# ArduinoProMini_Schematic.net
KiCad netlist of a schematic drawn in Altium Designer
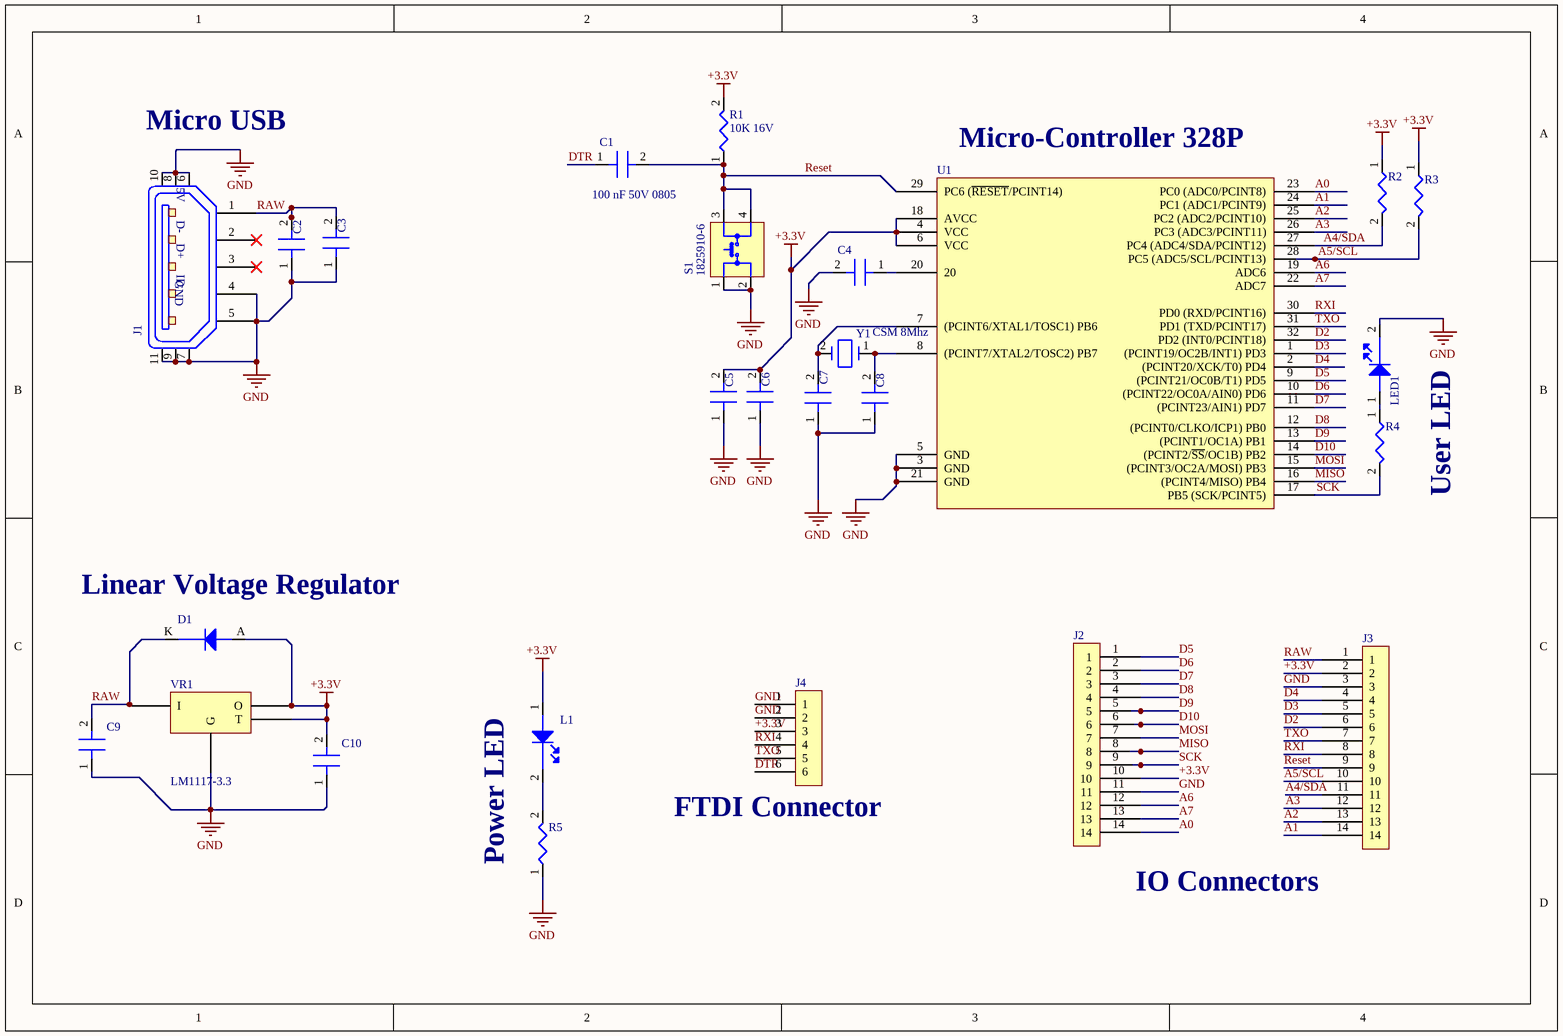
[diagram p0: ArduinoProMini_Schematic.SchDoc]

(export (version "E")
  (design (tool "Eeschema 10.0.6"))
  (components
    (comp (ref "C1")
      (value "100 nF 50V 0805")
      (footprint "C 0805")
      (description "Multilayer Ceramic Capacitor, 0.1 uF, 50 V, -20%, +80%, Y5V, 0805 [2012 Metric]")
      (fields
        (field (name "MANUFACTURER") "KEMET")
        (field (name "MANUFACTURER PART NUMBER") "C0805C104Z5VACTU")
      )
      (libsource (lib "ArduinoProMini_SchematicLib") (part "C0805C104Z5VACTU"))
    )
    (comp (ref "C2")
      (value "100nF")
      (footprint "C 0805")
      (description "Multilayer Ceramic Capacitor, 0.1 uF, 50 V, -20%, +80%, Y5V, 0805 [2012 Metric]")
      (fields
        (field (name "MANUFACTURER") "KEMET")
        (field (name "MANUFACTURER PART NUMBER") "C0805C104Z5VACTU")
      )
      (libsource (lib "ArduinoProMini_SchematicLib") (part "C0805C104Z5VACTU"))
    )
    (comp (ref "C3")
      (value "100nF")
      (footprint "C 0805")
      (description "Multilayer Ceramic Capacitor, 0.1 uF, 50 V, -20%, +80%, Y5V, 0805 [2012 Metric]")
      (fields
        (field (name "MANUFACTURER") "KEMET")
        (field (name "MANUFACTURER PART NUMBER") "C0805C104Z5VACTU")
      )
      (libsource (lib "ArduinoProMini_SchematicLib") (part "C0805C104Z5VACTU"))
    )
    (comp (ref "C4")
      (value "100 nF 50V 0805")
      (footprint "C 0805")
      (description "Multilayer Ceramic Capacitor, 0.1 uF, 50 V, -20%, +80%, Y5V, 0805 [2012 Metric]")
      (fields
        (field (name "MANUFACTURER") "KEMET")
        (field (name "MANUFACTURER PART NUMBER") "C0805C104Z5VACTU")
      )
      (libsource (lib "ArduinoProMini_SchematicLib") (part "C0805C104Z5VACTU"))
    )
    (comp (ref "C5")
      (value "100 nF 50V 0805")
      (footprint "C 0805")
      (description "Multilayer Ceramic Capacitor, 0.1 uF, 50 V, -20%, +80%, Y5V, 0805 [2012 Metric]")
      (fields
        (field (name "MANUFACTURER") "KEMET")
        (field (name "MANUFACTURER PART NUMBER") "C0805C104Z5VACTU")
      )
      (libsource (lib "ArduinoProMini_SchematicLib") (part "C0805C104Z5VACTU"))
    )
    (comp (ref "C6")
      (value "100 nF 50V 0805")
      (footprint "C 0805")
      (description "Multilayer Ceramic Capacitor, 0.1 uF, 50 V, -20%, +80%, Y5V, 0805 [2012 Metric]")
      (fields
        (field (name "MANUFACTURER") "KEMET")
        (field (name "MANUFACTURER PART NUMBER") "C0805C104Z5VACTU")
      )
      (libsource (lib "ArduinoProMini_SchematicLib") (part "C0805C104Z5VACTU"))
    )
    (comp (ref "C7")
      (value "18pF")
      (footprint "C 0805")
      (description "Multilayer Ceramic Capacitor, 18 pF, 50 V, ± 5%, C0G (NP0), 0805 [2012 Metric]")
      (fields
        (field (name "MANUFACTURER") "Yageo")
        (field (name "MANUFACTURER PART NUMBER") "CC0805JRNPO9BN180")
      )
      (libsource (lib "ArduinoProMini_SchematicLib") (part "CC0805JRNPO9BN180"))
    )
    (comp (ref "C8")
      (value "18pF")
      (footprint "C 0805")
      (description "Multilayer Ceramic Capacitor, 18 pF, 50 V, ± 5%, C0G (NP0), 0805 [2012 Metric]")
      (fields
        (field (name "MANUFACTURER") "Yageo")
        (field (name "MANUFACTURER PART NUMBER") "CC0805JRNPO9BN180")
      )
      (libsource (lib "ArduinoProMini_SchematicLib") (part "CC0805JRNPO9BN180"))
    )
    (comp (ref "C9")
      (value "10uF 16V")
      (footprint "C 0805")
      (description "Multilayer Ceramic Capacitor, 10 uF, 16 V, ± 10%, X5R, 0805 [2012 Metric]")
      (fields
        (field (name "MANUFACTURER") "KEMET")
        (field (name "MANUFACTURER PART NUMBER") "C0805C106K4PACTU")
      )
      (libsource (lib "ArduinoProMini_SchematicLib") (part "C0805C106K4PACTU"))
    )
    (comp (ref "C10")
      (value "10uF")
      (footprint "C 0805")
      (description "Multilayer Ceramic Capacitor, 10 uF, 16 V, ± 10%, X5R, 0805 [2012 Metric]")
      (fields
        (field (name "MANUFACTURER") "KEMET")
        (field (name "MANUFACTURER PART NUMBER") "C0805C106K4PACTU")
      )
      (libsource (lib "ArduinoProMini_SchematicLib") (part "C0805C106K4PACTU"))
    )
    (comp (ref "D1")
      (value "1N4148")
      (footprint "DIode 1N4148")
      (description "Rectifier Diode Switching 75V 0.2A 5ns 2-Pin DO-213AA Bag")
      (fields
        (field (name "MANUFACTURER") "Microsemi")
        (field (name "MANUFACTURER PART NUMBER") "1N4148UR-1")
      )
      (libsource (lib "ArduinoProMini_SchematicLib") (part "1N4148UR-1"))
    )
    (comp (ref "J1")
      (value "~")
      (footprint "Micro-USB-Type-B-FP")
      (description "CONN USB MICRO B RECPT SMT R/A")
      (fields
        (field (name "MANUFACTURER") "Amphenol ICC / FCI")
        (field (name "MANUFACTURER PART NUMBER") "10118194-0001LF")
      )
      (libsource (lib "ArduinoProMini_SchematicLib") (part "Micro-USB-Type-B-SCH"))
    )
    (comp (ref "J2")
      (value "Header 1*14 Male 2.54")
      (footprint "Header Male 1x14 2.54")
      (description "Conn Unshrouded Header HDR 14 POS 2.54mm Solder ST Thru-Hole Bag")
      (fields
        (field (name "MANUFACTURER") "Adam Equipment")
        (field (name "MANUFACTURER PART NUMBER") "PH1-14-UA")
      )
      (libsource (lib "") (part "PH1-14-UA_1"))
    )
    (comp (ref "J3")
      (value "Header 1*14 Male 2.54")
      (footprint "Header Male 1x14 2.54")
      (description "Conn Unshrouded Header HDR 14 POS 2.54mm Solder ST Thru-Hole Bag")
      (fields
        (field (name "MANUFACTURER") "Adam Equipment")
        (field (name "MANUFACTURER PART NUMBER") "PH1-14-UA")
      )
      (libsource (lib "ArduinoProMini_SchematicLib") (part "PH1-14-UA"))
    )
    (comp (ref "J4")
      (value "Header 1*6 Female")
      (footprint "Header Female 1x6-254")
      (description "2.54mm (0.1\") Pitch SIL Vertical PC Tail Socket Assembly, tin, 6 contacts")
      (fields (field (name "MANUFACTURER") "Harwin") (field (name "MANUFACTURER PART NUMBER") "M20-7820646"))
      (libsource (lib "ArduinoProMini_SchematicLib") (part "M20-7820646"))
    )
    (comp (ref "L1")
      (value "LED Blue 0603")
      (footprint "LED 0603")
      (description "LED BLUE CLEAR 0603 SMD")
      (fields
        (field (name "MANUFACTURER") "Vishay Lite-On")
        (field (name "MANUFACTURER PART NUMBER") "LTST-C194TBKT")
      )
      (libsource (lib "ArduinoProMini_SchematicLib") (part "LTST-C194TBKT"))
    )
    (comp (ref "LED1")
      (value "LED White 0603")
      (footprint "LED 0603")
      (fields (field (name "MANUFACTURER") "Inolux") (field (name "MANUFACTURER PART NUMBER") "IN-S63AT5UW"))
      (libsource (lib "ArduinoProMini_SchematicLib") (part "IN-S63AT5UW"))
    )
    (comp (ref "R1")
      (value "10K 16V")
      (footprint "R 0805")
      (description "SMD Chip Resistor, 10 kOhm, ± 1%, 125 mW, 0805 [2012 Metric], Thick Film, General Purpose")
      (fields
        (field (name "MANUFACTURER") "Yageo")
        (field (name "MANUFACTURER PART NUMBER") "RC0805FR-0710KL")
      )
      (libsource (lib "ArduinoProMini_SchematicLib") (part "RC0805FR-0710KL"))
    )
    (comp (ref "R2")
      (value "10K 16V")
      (footprint "R 0805")
      (description "SMD Chip Resistor, 10 kOhm, ± 1%, 125 mW, 0805 [2012 Metric], Thick Film, General Purpose")
      (fields
        (field (name "MANUFACTURER") "Yageo")
        (field (name "MANUFACTURER PART NUMBER") "RC0805FR-0710KL")
      )
      (libsource (lib "ArduinoProMini_SchematicLib") (part "RC0805FR-0710KL"))
    )
    (comp (ref "R3")
      (value "10K 16V")
      (footprint "R 0805")
      (description "SMD Chip Resistor, 10 kOhm, ± 1%, 125 mW, 0805 [2012 Metric], Thick Film, General Purpose")
      (fields
        (field (name "MANUFACTURER") "Yageo")
        (field (name "MANUFACTURER PART NUMBER") "RC0805FR-0710KL")
      )
      (libsource (lib "ArduinoProMini_SchematicLib") (part "RC0805FR-0710KL"))
    )
    (comp (ref "R4")
      (value "330R 150V")
      (footprint "R 0805")
      (description "SMD Chip Resistor, 330 Ohm, ± 5%, 125 mW, 0805 [2012 Metric], Thick Film, General Purpose")
      (fields
        (field (name "MANUFACTURER") "Yageo")
        (field (name "MANUFACTURER PART NUMBER") "RC0805JR-07330RL")
      )
      (libsource (lib "ArduinoProMini_SchematicLib") (part "RC0805JR-07330RL"))
    )
    (comp (ref "R5")
      (value "330R 150V")
      (footprint "R 0805")
      (description "SMD Chip Resistor, 330 Ohm, ± 5%, 125 mW, 0805 [2012 Metric], Thick Film, General Purpose")
      (fields
        (field (name "MANUFACTURER") "Yageo")
        (field (name "MANUFACTURER PART NUMBER") "RC0805JR-07330RL")
      )
      (libsource (lib "ArduinoProMini_SchematicLib") (part "RC0805JR-07330RL"))
    )
    (comp (ref "S1")
      (value "1825910-6")
      (footprint "SW-1825910-6")
      (description "Alcoswitch, Switch, Pushbutton, Tactile, SPST, 50mA, Thru Hole, 6mm ¦ TE Connectivity FSM4JH")
      (fields (field (name "MANUFACTURER") "TE Connectivity Alcoswitch"))
      (libsource (lib "ArduinoProMini_SchematicLib") (part "1825910-6"))
    )
    (comp (ref "U1")
      (value "ATMEGA328P-AUR")
      (footprint "TQFP-32")
      (description "1.8V~5.5V AVR 2MHz 23 TQFP-32 Microcontroller Units (MCUs/MPUs/SOCs) ROHS")
      (fields (field (name "MANUFACTURER") "Microchip"))
      (libsource (lib "ArduinoProMini_SchematicLib") (part "ATMEGA328P-AUR"))
    )
    (comp (ref "VR1")
      (value "LM1117-3.3")
      (footprint "LM1117-SOT223")
      (description "Positive Voltage Regulator, LDO, 3.3V, 0.8A, 1%, 1.2V dropout, 0÷125°C; LM1117MPX-3.3/NOPB")
      (fields
        (field (name "MANUFACTURER") "Texas Instruments")
        (field (name "MANUFACTURER PART NUMBER") "LM1117MPX-3.3/NOPB")
      )
      (libsource (lib "ArduinoProMini_SchematicLib") (part "LM1117MPX-3.3/NOPB"))
    )
    (comp (ref "Y1")
      (value "CSM 8Mhz")
      (footprint "Crystal CSM-7X")
      (description "Crystal 8MHz ±30ppm (Tol) ±50ppm (Stability) 18pF FUND 60Ohm 2-Pin HC-49/USX SMD T/R")
      (fields
        (field (name "MANUFACTURER") "ECS International")
        (field (name "MANUFACTURER PART NUMBER") "ECS-80-18-5PX-TR")
      )
      (libsource (lib "ArduinoProMini_SchematicLib") (part "ECS-80-18-5PX-TR"))
    )
  )
  (nets
    (net (code "1") (name "+3.3V") (class "Default")
      (node (ref "C10") (pin "2") (pinfunction "2_2") (pintype "passive"))
      (node (ref "C5") (pin "2") (pinfunction "2_2") (pintype "passive"))
      (node (ref "C6") (pin "2") (pinfunction "2_2") (pintype "passive"))
      (node (ref "D1") (pin "A") (pinfunction "anode_A") (pintype "passive"))
      (node (ref "J2") (pin "10") (pinfunction "10_10") (pintype "passive"))
      (node (ref "J3") (pin "2") (pinfunction "2_2") (pintype "passive"))
      (node (ref "J4") (pin "3") (pinfunction "3_3") (pintype "passive"))
      (node (ref "L1") (pin "1") (pinfunction "anode_1") (pintype "passive"))
      (node (ref "R1") (pin "2") (pinfunction "2_2") (pintype "passive"))
      (node (ref "R2") (pin "1") (pinfunction "1_1") (pintype "passive"))
      (node (ref "R3") (pin "1") (pinfunction "1_1") (pintype "passive"))
      (node (ref "U1") (pin "18") (pinfunction "AVCC_18") (pintype "passive"))
      (node (ref "U1") (pin "4") (pinfunction "VCC_4") (pintype "passive"))
      (node (ref "U1") (pin "6") (pinfunction "VCC_6") (pintype "passive"))
      (node (ref "VR1") (pin "2") (pinfunction "O_2") (pintype "passive"))
      (node (ref "VR1") (pin "4") (pinfunction "T_4") (pintype "passive"))
    )
    (net (code "2") (name "/A0") (class "Default")
      (node (ref "J2") (pin "14") (pinfunction "14_14") (pintype "passive"))
      (node (ref "U1") (pin "23") (pinfunction "PC0_(ADC0/PCINT8)_23") (pintype "passive"))
    )
    (net (code "3") (name "/A1") (class "Default")
      (node (ref "J3") (pin "14") (pinfunction "14_14") (pintype "passive"))
      (node (ref "U1") (pin "24") (pinfunction "PC1_(ADC1/PCINT9)_24") (pintype "passive"))
    )
    (net (code "4") (name "/A2") (class "Default")
      (node (ref "J3") (pin "13") (pinfunction "13_13") (pintype "passive"))
      (node (ref "U1") (pin "25") (pinfunction "PC2_(ADC2/PCINT10)_25") (pintype "passive"))
    )
    (net (code "5") (name "/A3") (class "Default")
      (node (ref "J3") (pin "12") (pinfunction "12_12") (pintype "passive"))
      (node (ref "U1") (pin "26") (pinfunction "PC3_(ADC3/PCINT11)_26") (pintype "passive"))
    )
    (net (code "6") (name "/A4{slash}SDA") (class "Default")
      (node (ref "J3") (pin "11") (pinfunction "11_11") (pintype "passive"))
      (node (ref "R2") (pin "2") (pinfunction "2_2") (pintype "passive"))
      (node (ref "U1") (pin "27") (pinfunction "PC4_(ADC4/SDA/PCINT12)_27") (pintype "passive"))
    )
    (net (code "7") (name "/A5{slash}SCL") (class "Default")
      (node (ref "J3") (pin "10") (pinfunction "10_10") (pintype "passive"))
      (node (ref "R3") (pin "2") (pinfunction "2_2") (pintype "passive"))
      (node (ref "U1") (pin "28") (pinfunction "PC5_(ADC5/SCL/PCINT13)_28") (pintype "passive"))
    )
    (net (code "8") (name "/A6") (class "Default")
      (node (ref "J2") (pin "12") (pinfunction "12_12") (pintype "passive"))
      (node (ref "U1") (pin "19") (pinfunction "ADC6_19") (pintype "passive"))
    )
    (net (code "9") (name "/A7") (class "Default")
      (node (ref "J2") (pin "13") (pinfunction "13_13") (pintype "passive"))
      (node (ref "U1") (pin "22") (pinfunction "ADC7_22") (pintype "passive"))
    )
    (net (code "10") (name "/D2") (class "Default")
      (node (ref "J3") (pin "6") (pinfunction "6_6") (pintype "passive"))
      (node (ref "U1") (pin "32") (pinfunction "PD2_(INT0/PCINT18)_32") (pintype "passive"))
    )
    (net (code "11") (name "/D3") (class "Default")
      (node (ref "J3") (pin "5") (pinfunction "5_5") (pintype "passive"))
      (node (ref "U1") (pin "1") (pinfunction "(PCINT19/OC2B/INT1)_PD3_1") (pintype "passive"))
    )
    (net (code "12") (name "/D4") (class "Default")
      (node (ref "J3") (pin "4") (pinfunction "4_4") (pintype "passive"))
      (node (ref "U1") (pin "2") (pinfunction "(PCINT20/XCK/T0)_PD4_2") (pintype "passive"))
    )
    (net (code "13") (name "/D5") (class "Default")
      (node (ref "J2") (pin "1") (pinfunction "1_1") (pintype "passive"))
      (node (ref "U1") (pin "9") (pinfunction "(PCINT21/OC0B/T1)_PD5_9") (pintype "passive"))
    )
    (net (code "14") (name "/D6") (class "Default")
      (node (ref "J2") (pin "2") (pinfunction "2_2") (pintype "passive"))
      (node (ref "U1") (pin "10") (pinfunction "(PCINT22/OC0A/AIN0)_PD6_10") (pintype "passive"))
    )
    (net (code "15") (name "/D7") (class "Default")
      (node (ref "J2") (pin "3") (pinfunction "3_3") (pintype "passive"))
      (node (ref "U1") (pin "11") (pinfunction "(PCINT23/AIN1)_PD7_11") (pintype "passive"))
    )
    (net (code "16") (name "/D8") (class "Default")
      (node (ref "J2") (pin "4") (pinfunction "4_4") (pintype "passive"))
      (node (ref "U1") (pin "12") (pinfunction "(PCINT0/CLKO/ICP1)_PB0_12") (pintype "passive"))
    )
    (net (code "17") (name "/D9") (class "Default")
      (node (ref "J2") (pin "5") (pinfunction "5_5") (pintype "passive"))
      (node (ref "U1") (pin "13") (pinfunction "(PCINT1/OC1A)_PB1_13") (pintype "passive"))
    )
    (net (code "18") (name "/D10") (class "Default")
      (node (ref "J2") (pin "6") (pinfunction "6_6") (pintype "passive"))
      (node (ref "U1") (pin "14") (pinfunction "(PCINT2/~{SS}/OC1B)_PB2_14") (pintype "passive"))
    )
    (net (code "19") (name "/DTR") (class "Default")
      (node (ref "C1") (pin "1") (pinfunction "1_1") (pintype "passive"))
      (node (ref "J4") (pin "6") (pinfunction "6_6") (pintype "passive"))
    )
    (net (code "20") (name "/MISO") (class "Default")
      (node (ref "J2") (pin "8") (pinfunction "8_8") (pintype "passive"))
      (node (ref "U1") (pin "16") (pinfunction "(PCINT4/MISO)_PB4_16") (pintype "passive"))
    )
    (net (code "21") (name "/MOSI") (class "Default")
      (node (ref "J2") (pin "7") (pinfunction "7_7") (pintype "passive"))
      (node (ref "U1") (pin "15") (pinfunction "(PCINT3/OC2A/MOSI)_PB3_15") (pintype "passive"))
    )
    (net (code "22") (name "/RAW") (class "Default")
      (node (ref "C2") (pin "2") (pinfunction "2_2") (pintype "passive"))
      (node (ref "C3") (pin "2") (pinfunction "2_2") (pintype "passive"))
      (node (ref "C9") (pin "2") (pinfunction "2_2") (pintype "passive"))
      (node (ref "D1") (pin "K") (pinfunction "cathode_K") (pintype "passive"))
      (node (ref "J1") (pin "1") (pinfunction "1_1") (pintype "passive"))
      (node (ref "J3") (pin "1") (pinfunction "1_1") (pintype "passive"))
      (node (ref "VR1") (pin "3") (pinfunction "I_3") (pintype "passive"))
    )
    (net (code "23") (name "/RXI") (class "Default")
      (node (ref "J3") (pin "8") (pinfunction "8_8") (pintype "passive"))
      (node (ref "J4") (pin "4") (pinfunction "4_4") (pintype "passive"))
      (node (ref "U1") (pin "30") (pinfunction "PD0_(RXD/PCINT16)_30") (pintype "passive"))
    )
    (net (code "24") (name "/Reset") (class "Default")
      (node (ref "C1") (pin "2") (pinfunction "2_2") (pintype "passive"))
      (node (ref "J3") (pin "9") (pinfunction "9_9") (pintype "passive"))
      (node (ref "R1") (pin "1") (pinfunction "1_1") (pintype "passive"))
      (node (ref "S1") (pin "3") (pinfunction "3_3") (pintype "passive"))
      (node (ref "S1") (pin "4") (pinfunction "4_4") (pintype "passive"))
      (node (ref "U1") (pin "29") (pinfunction "PC6_(~{RESET}/PCINT14)_29") (pintype "passive"))
    )
    (net (code "25") (name "/SCK") (class "Default")
      (node (ref "J2") (pin "9") (pinfunction "9_9") (pintype "passive"))
      (node (ref "R4") (pin "2") (pinfunction "2_2") (pintype "passive"))
      (node (ref "U1") (pin "17") (pinfunction "PB5_(SCK/PCINT5)_17") (pintype "passive"))
    )
    (net (code "26") (name "/TXO") (class "Default")
      (node (ref "J3") (pin "7") (pinfunction "7_7") (pintype "passive"))
      (node (ref "J4") (pin "5") (pinfunction "5_5") (pintype "passive"))
      (node (ref "U1") (pin "31") (pinfunction "PD1_(TXD/PCINT17)_31") (pintype "passive"))
    )
    (net (code "27") (name "GND") (class "Default")
      (node (ref "C10") (pin "1") (pinfunction "1_1") (pintype "passive"))
      (node (ref "C2") (pin "1") (pinfunction "1_1") (pintype "passive"))
      (node (ref "C3") (pin "1") (pinfunction "1_1") (pintype "passive"))
      (node (ref "C4") (pin "2") (pinfunction "2_2") (pintype "passive"))
      (node (ref "C5") (pin "1") (pinfunction "1_1") (pintype "passive"))
      (node (ref "C6") (pin "1") (pinfunction "1_1") (pintype "passive"))
      (node (ref "C7") (pin "1") (pinfunction "1_1") (pintype "passive"))
      (node (ref "C8") (pin "1") (pinfunction "1_1") (pintype "passive"))
      (node (ref "C9") (pin "1") (pinfunction "1_1") (pintype "passive"))
      (node (ref "J1") (pin "10") (pinfunction "10_10") (pintype "passive"))
      (node (ref "J1") (pin "11") (pinfunction "11_11") (pintype "passive"))
      (node (ref "J1") (pin "4") (pinfunction "4_4") (pintype "passive"))
      (node (ref "J1") (pin "5") (pinfunction "5_5") (pintype "passive"))
      (node (ref "J1") (pin "6") (pinfunction "6_6") (pintype "passive"))
      (node (ref "J1") (pin "7") (pinfunction "7_7") (pintype "passive"))
      (node (ref "J1") (pin "8") (pinfunction "8_8") (pintype "passive"))
      (node (ref "J1") (pin "9") (pinfunction "9_9") (pintype "passive"))
      (node (ref "J2") (pin "11") (pinfunction "11_11") (pintype "passive"))
      (node (ref "J3") (pin "3") (pinfunction "3_3") (pintype "passive"))
      (node (ref "J4") (pin "1") (pinfunction "1_1") (pintype "passive"))
      (node (ref "J4") (pin "2") (pinfunction "2_2") (pintype "passive"))
      (node (ref "LED1") (pin "2") (pinfunction "cathode_2") (pintype "passive"))
      (node (ref "R5") (pin "1") (pinfunction "1_1") (pintype "passive"))
      (node (ref "S1") (pin "1") (pinfunction "1_1") (pintype "passive"))
      (node (ref "S1") (pin "2") (pinfunction "2_2") (pintype "passive"))
      (node (ref "U1") (pin "21") (pinfunction "GND_21") (pintype "passive"))
      (node (ref "U1") (pin "3") (pinfunction "GND_3") (pintype "passive"))
      (node (ref "U1") (pin "5") (pinfunction "GND_5") (pintype "passive"))
      (node (ref "VR1") (pin "1") (pinfunction "G_1") (pintype "passive"))
    )
    (net (code "28") (name "Net-(C4-Pad1)") (class "Default")
      (node (ref "C4") (pin "1") (pinfunction "1_1") (pintype "passive"))
      (node (ref "U1") (pin "20") (pinfunction "20_20") (pintype "passive"))
    )
    (net (code "29") (name "Net-(L1-cathode)") (class "Default")
      (node (ref "L1") (pin "2") (pinfunction "cathode_2") (pintype "passive"))
      (node (ref "R5") (pin "2") (pinfunction "2_2") (pintype "passive"))
    )
    (net (code "30") (name "Net-(LED1-anode)") (class "Default")
      (node (ref "LED1") (pin "1") (pinfunction "anode_1") (pintype "passive"))
      (node (ref "R4") (pin "1") (pinfunction "1_1") (pintype "passive"))
    )
    (net (code "31") (name "Net-(U1-(PCINT6{slash}XTAL1{slash}TOSC1)_PB6)") (class "Default")
      (node (ref "C7") (pin "2") (pinfunction "2_2") (pintype "passive"))
      (node (ref "U1") (pin "7") (pinfunction "(PCINT6/XTAL1/TOSC1)_PB6_7") (pintype "passive"))
      (node (ref "Y1") (pin "2") (pinfunction "2_2") (pintype "passive"))
    )
    (net (code "32") (name "Net-(U1-(PCINT7{slash}XTAL2{slash}TOSC2)_PB7)") (class "Default")
      (node (ref "C8") (pin "2") (pinfunction "2_2") (pintype "passive"))
      (node (ref "U1") (pin "8") (pinfunction "(PCINT7/XTAL2/TOSC2)_PB7_8") (pintype "passive"))
      (node (ref "Y1") (pin "1") (pinfunction "1_1") (pintype "passive"))
    )
    (net (code "33") (name "unconnected-(J1-Pad2)") (class "Default")
      (node (ref "J1") (pin "2") (pinfunction "2_2") (pintype "passive+no_connect"))
    )
    (net (code "34") (name "unconnected-(J1-Pad3)") (class "Default")
      (node (ref "J1") (pin "3") (pinfunction "3_3") (pintype "passive+no_connect"))
    )
  )
)
